# sensor.net
KiCad netlist of a schematic drawn in EAGLE
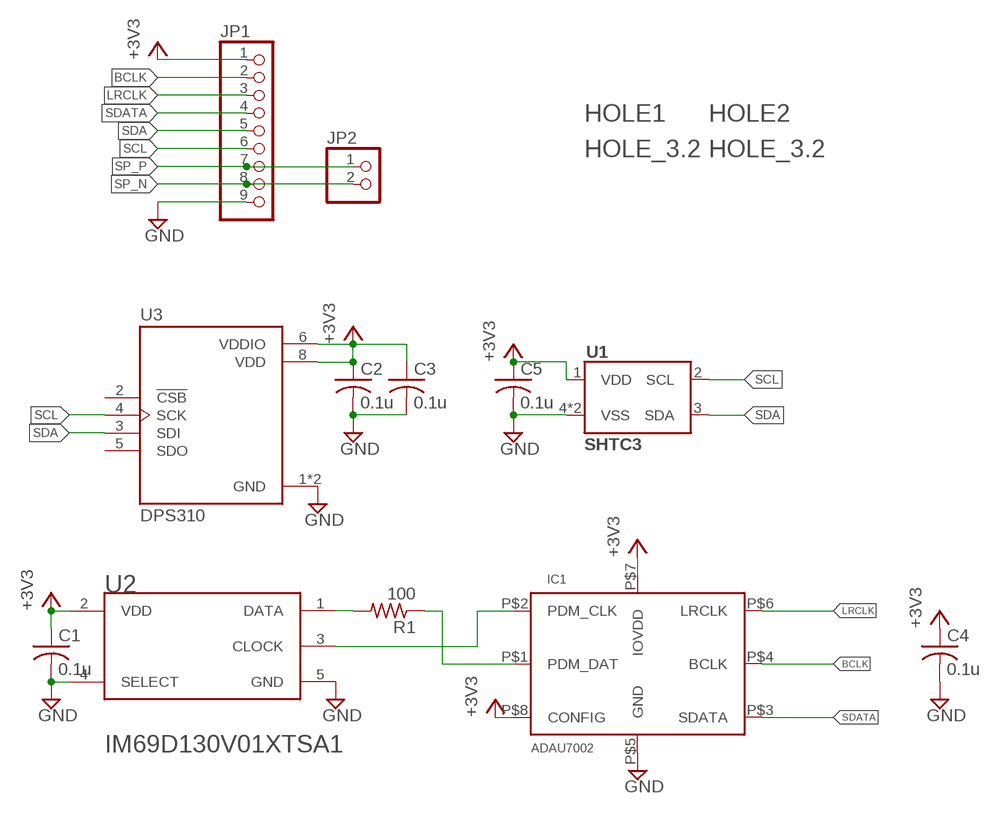
[diagram p0: schematic, sheet 1]

(export (version "E")
  (design (tool "Eeschema 10.0.6"))
  (components
    (comp (ref "C1")
      (value "0.1u")
      (footprint "eagle-import:2012-C")
      (libsource (lib "eagle-import") (part "C-2012"))
    )
    (comp (ref "C2")
      (value "0.1u")
      (footprint "eagle-import:2012-C")
      (libsource (lib "eagle-import") (part "C-2012"))
    )
    (comp (ref "C3")
      (value "0.1u")
      (footprint "eagle-import:2012-C")
      (libsource (lib "eagle-import") (part "C-2012"))
    )
    (comp (ref "C4")
      (value "0.1u")
      (footprint "eagle-import:2012-C")
      (libsource (lib "eagle-import") (part "C-2012"))
    )
    (comp (ref "C5")
      (value "0.1u")
      (footprint "eagle-import:2012-C")
      (libsource (lib "eagle-import") (part "C-2012"))
    )
    (comp (ref "HOLE1")
      (value "HOLE_3.2")
      (footprint "eagle-import:HOLE_3.2")
      (libsource (lib "eagle-import") (part "HOLE_3.2"))
    )
    (comp (ref "HOLE2")
      (value "HOLE_3.2")
      (footprint "eagle-import:HOLE_3.2")
      (libsource (lib "eagle-import") (part "HOLE_3.2"))
    )
    (comp (ref "IC1")
      (value "ADAU7002")
      (footprint "eagle-import:WLCSP2X4")
      (libsource (lib "eagle-import") (part "ADAU7002"))
    )
    (comp (ref "JP1")
      (value "PINHD-1X9")
      (footprint "eagle-import:1X09")
      (libsource (lib "eagle-import") (part "PINHD-1X9"))
    )
    (comp (ref "JP2")
      (value "PINHD-1X2")
      (footprint "eagle-import:1X02")
      (libsource (lib "eagle-import") (part "PINHD-1X2"))
    )
    (comp (ref "R1")
      (value "100")
      (footprint "eagle-import:2012-R")
      (libsource (lib "eagle-import") (part "R-2012"))
    )
    (comp (ref "U1")
      (value "SHTC3")
      (footprint "eagle-import:SHTC3")
      (libsource (lib "eagle-import") (part "SHTC3"))
    )
    (comp (ref "U2")
      (value "IM69D130")
      (footprint "eagle-import:IM69D130")
      (libsource (lib "eagle-import") (part "IM69D130"))
    )
    (comp (ref "U3")
      (value "DPS310")
      (footprint "eagle-import:XDCR_DPS310")
      (fields (field (name "MF") "Infineon Technologies"))
      (libsource (lib "eagle-import") (part "DPS310"))
    )
  )
  (nets
    (net (code "1") (name "+3V3") (class "Default")
      (node (ref "C1") (pin "1") (pinfunction "1_1") (pintype "passive"))
      (node (ref "C2") (pin "1") (pinfunction "1_1") (pintype "passive"))
      (node (ref "C3") (pin "1") (pinfunction "1_1") (pintype "passive"))
      (node (ref "C4") (pin "1") (pinfunction "1_1") (pintype "passive"))
      (node (ref "C5") (pin "1") (pinfunction "1_1") (pintype "passive"))
      (node (ref "IC1") (pin "P$7") (pinfunction "IOVDD_P$7") (pintype "passive"))
      (node (ref "IC1") (pin "P$8") (pinfunction "CONFIG_P$8") (pintype "input"))
      (node (ref "JP1") (pin "1") (pinfunction "1_1") (pintype "passive"))
      (node (ref "U1") (pin "1") (pinfunction "VDD_1") (pintype "bidirectional"))
      (node (ref "U2") (pin "2") (pinfunction "VDD_2") (pintype "power_in"))
      (node (ref "U3") (pin "6") (pinfunction "VDDIO_6") (pintype "power_in"))
      (node (ref "U3") (pin "8") (pinfunction "VDD_8") (pintype "power_in"))
    )
    (net (code "2") (name "BCLK") (class "Default")
      (node (ref "IC1") (pin "P$4") (pinfunction "BCLK_P$4") (pintype "output"))
      (node (ref "JP1") (pin "2") (pinfunction "2_2") (pintype "passive"))
    )
    (net (code "3") (name "GND") (class "Default")
      (node (ref "C1") (pin "2") (pinfunction "2_2") (pintype "passive"))
      (node (ref "C2") (pin "2") (pinfunction "2_2") (pintype "passive"))
      (node (ref "C3") (pin "2") (pinfunction "2_2") (pintype "passive"))
      (node (ref "C4") (pin "2") (pinfunction "2_2") (pintype "passive"))
      (node (ref "C5") (pin "2") (pinfunction "2_2") (pintype "passive"))
      (node (ref "IC1") (pin "P$5") (pinfunction "GND_P$5") (pintype "power_in"))
      (node (ref "JP1") (pin "9") (pinfunction "9_9") (pintype "passive"))
      (node (ref "U1") (pin "4") (pinfunction "VSS_4") (pintype "bidirectional"))
      (node (ref "U1") (pin "5") (pinfunction "VSS_5") (pintype "bidirectional"))
      (node (ref "U2") (pin "4") (pinfunction "SELECT_4") (pintype "input"))
      (node (ref "U2") (pin "5") (pinfunction "GND_5") (pintype "power_in"))
      (node (ref "U3") (pin "1") (pinfunction "GND_1") (pintype "power_in"))
      (node (ref "U3") (pin "7") (pinfunction "GND_7") (pintype "power_in"))
    )
    (net (code "4") (name "LRCLK") (class "Default")
      (node (ref "IC1") (pin "P$6") (pinfunction "LRCLK_P$6") (pintype "output"))
      (node (ref "JP1") (pin "3") (pinfunction "3_3") (pintype "passive"))
    )
    (net (code "5") (name "Net-(IC1-PDM_CLK)") (class "Default")
      (node (ref "IC1") (pin "P$2") (pinfunction "PDM_CLK_P$2") (pintype "input"))
      (node (ref "U2") (pin "3") (pinfunction "CLOCK_3") (pintype "input"))
    )
    (net (code "6") (name "Net-(IC1-PDM_DAT)") (class "Default")
      (node (ref "IC1") (pin "P$1") (pinfunction "PDM_DAT_P$1") (pintype "input"))
      (node (ref "R1") (pin "1") (pinfunction "1_1") (pintype "passive"))
    )
    (net (code "7") (name "Net-(U2-DATA)") (class "Default")
      (node (ref "R1") (pin "2") (pinfunction "2_2") (pintype "passive"))
      (node (ref "U2") (pin "1") (pinfunction "DATA_1") (pintype "output"))
    )
    (net (code "8") (name "SCL") (class "Default")
      (node (ref "JP1") (pin "6") (pinfunction "6_6") (pintype "passive"))
      (node (ref "U1") (pin "2") (pinfunction "SCL_2") (pintype "bidirectional"))
      (node (ref "U3") (pin "4") (pinfunction "SCK_4") (pintype "input"))
    )
    (net (code "9") (name "SDA") (class "Default")
      (node (ref "JP1") (pin "5") (pinfunction "5_5") (pintype "passive"))
      (node (ref "U1") (pin "3") (pinfunction "SDA_3") (pintype "bidirectional"))
      (node (ref "U3") (pin "3") (pinfunction "SDI_3") (pintype "bidirectional"))
    )
    (net (code "10") (name "SDATA") (class "Default")
      (node (ref "IC1") (pin "P$3") (pinfunction "SDATA_P$3") (pintype "output"))
      (node (ref "JP1") (pin "4") (pinfunction "4_4") (pintype "passive"))
    )
    (net (code "11") (name "SP_N") (class "Default")
      (node (ref "JP1") (pin "8") (pinfunction "8_8") (pintype "passive"))
      (node (ref "JP2") (pin "2") (pinfunction "2_2") (pintype "passive"))
    )
    (net (code "12") (name "SP_P") (class "Default")
      (node (ref "JP1") (pin "7") (pinfunction "7_7") (pintype "passive"))
      (node (ref "JP2") (pin "1") (pinfunction "1_1") (pintype "passive"))
    )
    (net (code "13") (name "unconnected-(U3-SDO-Pad5)") (class "Default")
      (node (ref "U3") (pin "5") (pinfunction "SDO_5") (pintype "output"))
    )
    (net (code "14") (name "unconnected-(U3-~{CSB}-Pad2)") (class "Default")
      (node (ref "U3") (pin "2") (pinfunction "~{CSB}_2") (pintype "input"))
    )
  )
)
